# breakout-r2.net
KiCad netlist of a schematic drawn in EAGLE
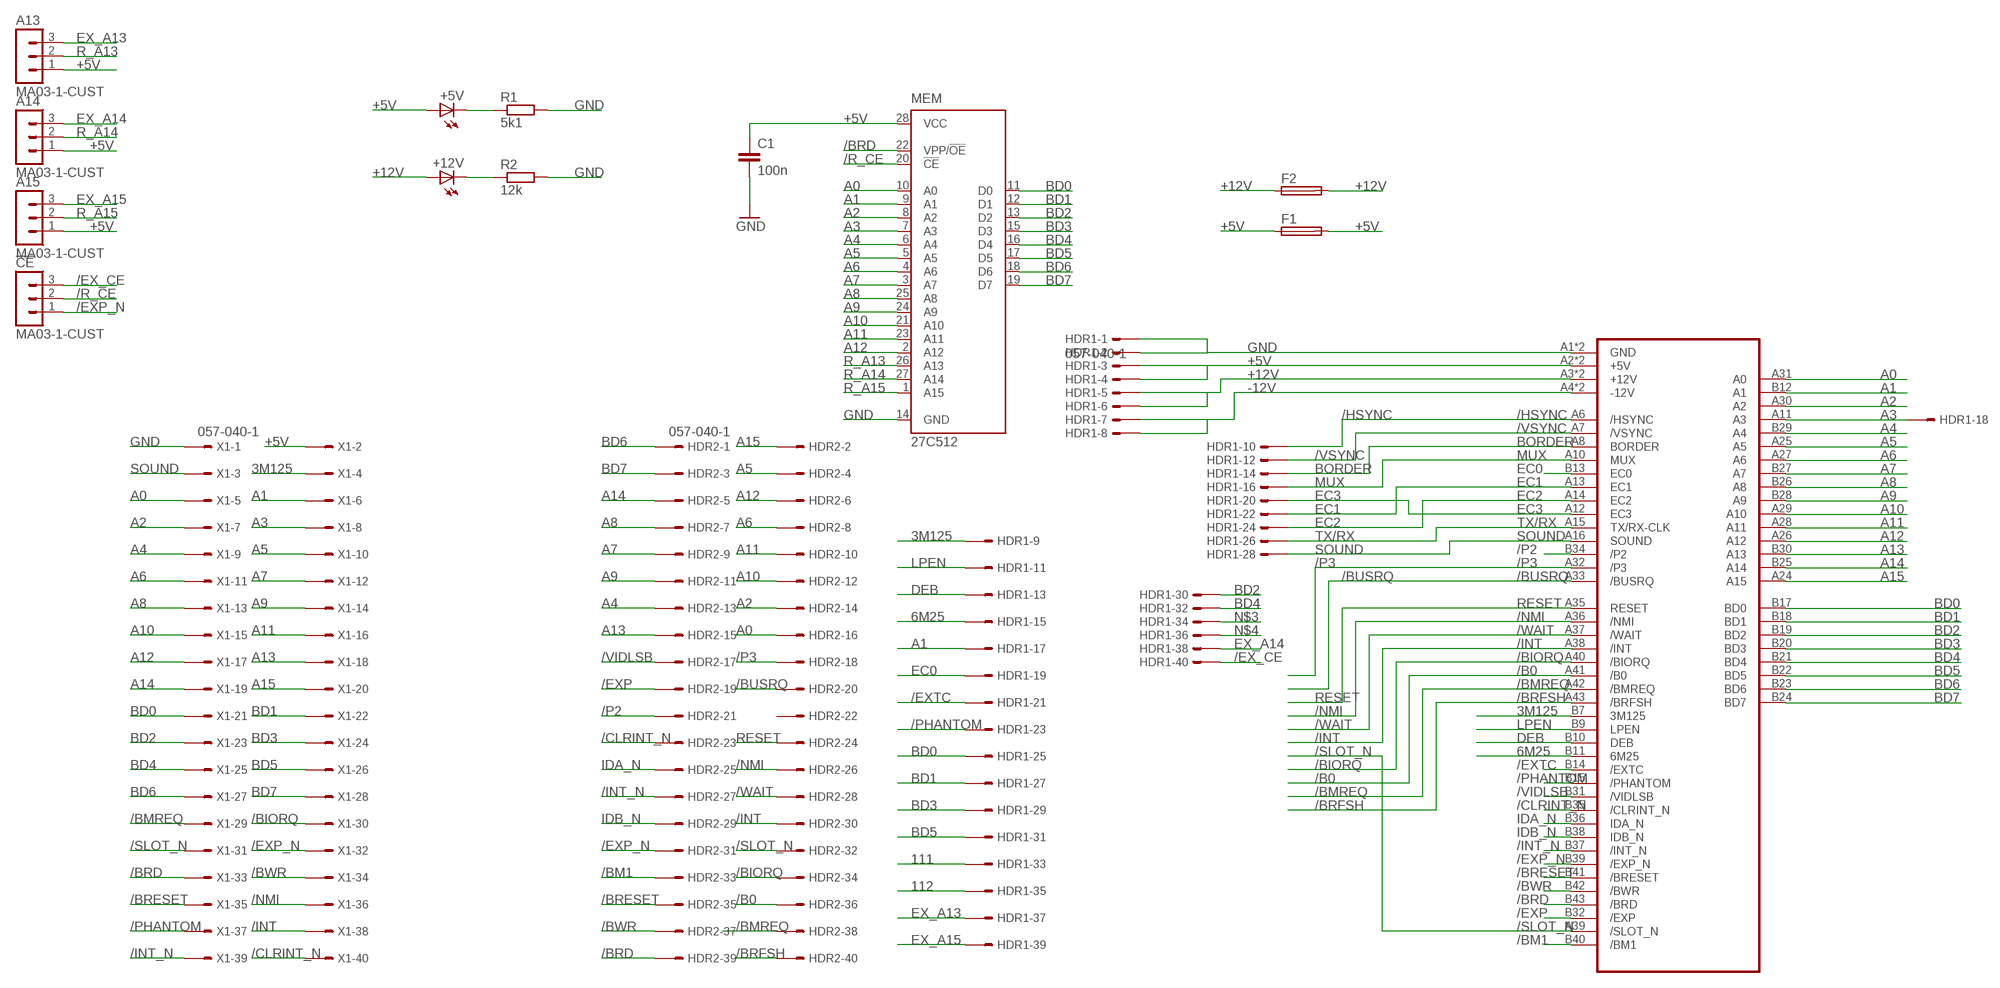
[diagram p0: schematic, sheet 1]

(export (version "E")
  (design (tool "Eeschema 10.0.6"))
  (components
    (comp (ref "!CE")
      (value "MA03-1-CUST")
      (footprint "eagle-import:MA03-1")
      (libsource (lib "eagle-import") (part "MA03-1-CUST"))
    )
    (comp (ref "+5V")
      (value "LED3MM")
      (footprint "eagle-import:LED3MM")
      (libsource (lib "eagle-import") (part "LED3MM"))
    )
    (comp (ref "+12V")
      (value "LED3MM")
      (footprint "eagle-import:LED3MM")
      (libsource (lib "eagle-import") (part "LED3MM"))
    )
    (comp (ref "A13")
      (value "MA03-1-CUST")
      (footprint "eagle-import:MA03-1")
      (libsource (lib "eagle-import") (part "MA03-1-CUST"))
    )
    (comp (ref "A14")
      (value "MA03-1-CUST")
      (footprint "eagle-import:MA03-1")
      (libsource (lib "eagle-import") (part "MA03-1-CUST"))
    )
    (comp (ref "A15")
      (value "MA03-1-CUST")
      (footprint "eagle-import:MA03-1")
      (libsource (lib "eagle-import") (part "MA03-1-CUST"))
    )
    (comp (ref "C1")
      (value "100n")
      (footprint "eagle-import:C025-025X050")
      (libsource (lib "eagle-import") (part "C-EU025-025X050"))
    )
    (comp (ref "F1")
      (value "TE5")
      (footprint "eagle-import:TE5")
      (libsource (lib "eagle-import") (part "TE5"))
    )
    (comp (ref "F2")
      (value "TE5")
      (footprint "eagle-import:TE5")
      (libsource (lib "eagle-import") (part "TE5"))
    )
    (comp (ref "HDR1")
      (value "057-040-1")
      (footprint "eagle-import:057-040-1")
      (libsource (lib "eagle-import") (part "057-040-1"))
    )
    (comp (ref "HDR2")
      (value "057-040-1")
      (footprint "eagle-import:057-040-1")
      (libsource (lib "eagle-import") (part "057-040-1"))
    )
    (comp (ref "MEM")
      (value "27C512")
      (footprint "eagle-import:DIL28-6")
      (libsource (lib "eagle-import") (part "W27C512"))
    )
    (comp (ref "R1")
      (value "5k1")
      (footprint "eagle-import:0204_7")
      (libsource (lib "eagle-import") (part "R-EU_0204/7"))
    )
    (comp (ref "R2")
      (value "12k")
      (footprint "eagle-import:0204_7")
      (libsource (lib "eagle-import") (part "R-EU_0204/7"))
    )
    (comp (ref "U$1")
      (value "TVC-EXP-HBA-COMMON")
      (footprint "eagle-import:TVC-EXP-EDGE")
      (libsource (lib "eagle-import") (part "TVC-EXP-HBA-COMMON"))
    )
    (comp (ref "X1")
      (value "057-040-1")
      (footprint "eagle-import:057-040-1")
      (libsource (lib "eagle-import") (part "057-040-1"))
    )
  )
  (nets
    (net (code "1") (name "/+5V") (class "Default")
      (node (ref "+5V") (pin "A") (pinfunction "A_A") (pintype "passive"))
      (node (ref "A13") (pin "1") (pinfunction "1_1") (pintype "passive"))
      (node (ref "A14") (pin "1") (pinfunction "1_1") (pintype "passive"))
      (node (ref "A15") (pin "1") (pinfunction "1_1") (pintype "passive"))
      (node (ref "C1") (pin "1") (pinfunction "1_1") (pintype "passive"))
      (node (ref "F1") (pin "1") (pinfunction "1_1") (pintype "passive"))
      (node (ref "F1") (pin "2") (pinfunction "2_2") (pintype "passive"))
      (node (ref "HDR1") (pin "3") (pinfunction "S_3") (pintype "passive"))
      (node (ref "HDR1") (pin "4") (pinfunction "S_4") (pintype "passive"))
      (node (ref "MEM") (pin "28") (pinfunction "VCC_28") (pintype "power_in"))
      (node (ref "U$1") (pin "A2") (pinfunction "+5V_A2") (pintype "power_in"))
      (node (ref "U$1") (pin "B2") (pinfunction "+5V_B2") (pintype "power_in"))
      (node (ref "X1") (pin "2") (pinfunction "S_2") (pintype "passive"))
    )
    (net (code "2") (name "/+12V") (class "Default")
      (node (ref "+12V") (pin "A") (pinfunction "A_A") (pintype "passive"))
      (node (ref "F2") (pin "1") (pinfunction "1_1") (pintype "passive"))
      (node (ref "F2") (pin "2") (pinfunction "2_2") (pintype "passive"))
      (node (ref "HDR1") (pin "5") (pinfunction "S_5") (pintype "passive"))
      (node (ref "HDR1") (pin "6") (pinfunction "S_6") (pintype "passive"))
      (node (ref "U$1") (pin "A3") (pinfunction "+12V_A3") (pintype "power_in"))
      (node (ref "U$1") (pin "B3") (pinfunction "+12V_B3") (pintype "power_in"))
    )
    (net (code "3") (name "/-12V") (class "Default")
      (node (ref "HDR1") (pin "7") (pinfunction "S_7") (pintype "passive"))
      (node (ref "HDR1") (pin "8") (pinfunction "S_8") (pintype "passive"))
      (node (ref "U$1") (pin "A4") (pinfunction "-12V_A4") (pintype "power_in"))
      (node (ref "U$1") (pin "B4") (pinfunction "-12V_B4") (pintype "power_in"))
    )
    (net (code "4") (name "/3M125") (class "Default")
      (node (ref "HDR1") (pin "9") (pinfunction "S_9") (pintype "passive"))
      (node (ref "U$1") (pin "B7") (pinfunction "3M125_B7") (pintype "bidirectional"))
      (node (ref "X1") (pin "4") (pinfunction "S_4") (pintype "passive"))
    )
    (net (code "5") (name "/6M25") (class "Default")
      (node (ref "HDR1") (pin "15") (pinfunction "S_15") (pintype "passive"))
      (node (ref "U$1") (pin "B11") (pinfunction "6M25_B11") (pintype "bidirectional"))
    )
    (net (code "6") (name "/111") (class "Default")
      (node (ref "HDR1") (pin "33") (pinfunction "S_33") (pintype "passive"))
    )
    (net (code "7") (name "/112") (class "Default")
      (node (ref "HDR1") (pin "35") (pinfunction "S_35") (pintype "passive"))
    )
    (net (code "8") (name "/A0") (class "Default")
      (node (ref "HDR2") (pin "16") (pinfunction "S_16") (pintype "passive"))
      (node (ref "MEM") (pin "10") (pinfunction "A0_10") (pintype "input"))
      (node (ref "U$1") (pin "A31") (pinfunction "A0_A31") (pintype "bidirectional"))
      (node (ref "X1") (pin "5") (pinfunction "S_5") (pintype "passive"))
    )
    (net (code "9") (name "/A1") (class "Default")
      (node (ref "HDR1") (pin "17") (pinfunction "S_17") (pintype "passive"))
      (node (ref "MEM") (pin "9") (pinfunction "A1_9") (pintype "input"))
      (node (ref "U$1") (pin "B12") (pinfunction "A1_B12") (pintype "bidirectional"))
      (node (ref "X1") (pin "6") (pinfunction "S_6") (pintype "passive"))
    )
    (net (code "10") (name "/A2") (class "Default")
      (node (ref "HDR2") (pin "14") (pinfunction "S_14") (pintype "passive"))
      (node (ref "MEM") (pin "8") (pinfunction "A2_8") (pintype "input"))
      (node (ref "U$1") (pin "A30") (pinfunction "A2_A30") (pintype "bidirectional"))
      (node (ref "X1") (pin "7") (pinfunction "S_7") (pintype "passive"))
    )
    (net (code "11") (name "/A3") (class "Default")
      (node (ref "HDR1") (pin "18") (pinfunction "S_18") (pintype "passive"))
      (node (ref "MEM") (pin "7") (pinfunction "A3_7") (pintype "input"))
      (node (ref "U$1") (pin "A11") (pinfunction "A3_A11") (pintype "bidirectional"))
      (node (ref "X1") (pin "8") (pinfunction "S_8") (pintype "passive"))
    )
    (net (code "12") (name "/A4") (class "Default")
      (node (ref "HDR2") (pin "13") (pinfunction "S_13") (pintype "passive"))
      (node (ref "MEM") (pin "6") (pinfunction "A4_6") (pintype "input"))
      (node (ref "U$1") (pin "B29") (pinfunction "A4_B29") (pintype "bidirectional"))
      (node (ref "X1") (pin "9") (pinfunction "S_9") (pintype "passive"))
    )
    (net (code "13") (name "/A5") (class "Default")
      (node (ref "HDR2") (pin "4") (pinfunction "S_4") (pintype "passive"))
      (node (ref "MEM") (pin "5") (pinfunction "A5_5") (pintype "input"))
      (node (ref "U$1") (pin "A25") (pinfunction "A5_A25") (pintype "bidirectional"))
      (node (ref "X1") (pin "10") (pinfunction "S_10") (pintype "passive"))
    )
    (net (code "14") (name "/A6") (class "Default")
      (node (ref "HDR2") (pin "8") (pinfunction "S_8") (pintype "passive"))
      (node (ref "MEM") (pin "4") (pinfunction "A6_4") (pintype "input"))
      (node (ref "U$1") (pin "A27") (pinfunction "A6_A27") (pintype "bidirectional"))
      (node (ref "X1") (pin "11") (pinfunction "S_11") (pintype "passive"))
    )
    (net (code "15") (name "/A7") (class "Default")
      (node (ref "HDR2") (pin "9") (pinfunction "S_9") (pintype "passive"))
      (node (ref "MEM") (pin "3") (pinfunction "A7_3") (pintype "input"))
      (node (ref "U$1") (pin "B27") (pinfunction "A7_B27") (pintype "bidirectional"))
      (node (ref "X1") (pin "12") (pinfunction "S_12") (pintype "passive"))
    )
    (net (code "16") (name "/A8") (class "Default")
      (node (ref "HDR2") (pin "7") (pinfunction "S_7") (pintype "passive"))
      (node (ref "MEM") (pin "25") (pinfunction "A8_25") (pintype "input"))
      (node (ref "U$1") (pin "B26") (pinfunction "A8_B26") (pintype "bidirectional"))
      (node (ref "X1") (pin "13") (pinfunction "S_13") (pintype "passive"))
    )
    (net (code "17") (name "/A9") (class "Default")
      (node (ref "HDR2") (pin "11") (pinfunction "S_11") (pintype "passive"))
      (node (ref "MEM") (pin "24") (pinfunction "A9_24") (pintype "input"))
      (node (ref "U$1") (pin "B28") (pinfunction "A9_B28") (pintype "bidirectional"))
      (node (ref "X1") (pin "14") (pinfunction "S_14") (pintype "passive"))
    )
    (net (code "18") (name "/A10") (class "Default")
      (node (ref "HDR2") (pin "12") (pinfunction "S_12") (pintype "passive"))
      (node (ref "MEM") (pin "21") (pinfunction "A10_21") (pintype "input"))
      (node (ref "U$1") (pin "A29") (pinfunction "A10_A29") (pintype "bidirectional"))
      (node (ref "X1") (pin "15") (pinfunction "S_15") (pintype "passive"))
    )
    (net (code "19") (name "/A11") (class "Default")
      (node (ref "HDR2") (pin "10") (pinfunction "S_10") (pintype "passive"))
      (node (ref "MEM") (pin "23") (pinfunction "A11_23") (pintype "input"))
      (node (ref "U$1") (pin "A28") (pinfunction "A11_A28") (pintype "bidirectional"))
      (node (ref "X1") (pin "16") (pinfunction "S_16") (pintype "passive"))
    )
    (net (code "20") (name "/A12") (class "Default")
      (node (ref "HDR2") (pin "6") (pinfunction "S_6") (pintype "passive"))
      (node (ref "MEM") (pin "2") (pinfunction "A12_2") (pintype "input"))
      (node (ref "U$1") (pin "A26") (pinfunction "A12_A26") (pintype "bidirectional"))
      (node (ref "X1") (pin "17") (pinfunction "S_17") (pintype "passive"))
    )
    (net (code "21") (name "/A13") (class "Default")
      (node (ref "HDR2") (pin "15") (pinfunction "S_15") (pintype "passive"))
      (node (ref "U$1") (pin "B30") (pinfunction "A13_B30") (pintype "bidirectional"))
      (node (ref "X1") (pin "18") (pinfunction "S_18") (pintype "passive"))
    )
    (net (code "22") (name "/A14") (class "Default")
      (node (ref "HDR2") (pin "5") (pinfunction "S_5") (pintype "passive"))
      (node (ref "U$1") (pin "B25") (pinfunction "A14_B25") (pintype "bidirectional"))
      (node (ref "X1") (pin "19") (pinfunction "S_19") (pintype "passive"))
    )
    (net (code "23") (name "/A15") (class "Default")
      (node (ref "HDR2") (pin "2") (pinfunction "S_2") (pintype "passive"))
      (node (ref "U$1") (pin "A24") (pinfunction "A15_A24") (pintype "bidirectional"))
      (node (ref "X1") (pin "20") (pinfunction "S_20") (pintype "passive"))
    )
    (net (code "24") (name "/BD0") (class "Default")
      (node (ref "HDR1") (pin "25") (pinfunction "S_25") (pintype "passive"))
      (node (ref "MEM") (pin "11") (pinfunction "D0_11") (pintype "tri_state"))
      (node (ref "U$1") (pin "B17") (pinfunction "BD0_B17") (pintype "bidirectional"))
      (node (ref "X1") (pin "21") (pinfunction "S_21") (pintype "passive"))
    )
    (net (code "25") (name "/BD1") (class "Default")
      (node (ref "HDR1") (pin "27") (pinfunction "S_27") (pintype "passive"))
      (node (ref "MEM") (pin "12") (pinfunction "D1_12") (pintype "tri_state"))
      (node (ref "U$1") (pin "B18") (pinfunction "BD1_B18") (pintype "bidirectional"))
      (node (ref "X1") (pin "22") (pinfunction "S_22") (pintype "passive"))
    )
    (net (code "26") (name "/BD2") (class "Default")
      (node (ref "HDR1") (pin "30") (pinfunction "S_30") (pintype "passive"))
      (node (ref "MEM") (pin "13") (pinfunction "D2_13") (pintype "tri_state"))
      (node (ref "U$1") (pin "B19") (pinfunction "BD2_B19") (pintype "bidirectional"))
      (node (ref "X1") (pin "23") (pinfunction "S_23") (pintype "passive"))
    )
    (net (code "27") (name "/BD3") (class "Default")
      (node (ref "HDR1") (pin "29") (pinfunction "S_29") (pintype "passive"))
      (node (ref "MEM") (pin "15") (pinfunction "D3_15") (pintype "tri_state"))
      (node (ref "U$1") (pin "B20") (pinfunction "BD3_B20") (pintype "bidirectional"))
      (node (ref "X1") (pin "24") (pinfunction "S_24") (pintype "passive"))
    )
    (net (code "28") (name "/BD4") (class "Default")
      (node (ref "HDR1") (pin "32") (pinfunction "S_32") (pintype "passive"))
      (node (ref "MEM") (pin "16") (pinfunction "D4_16") (pintype "tri_state"))
      (node (ref "U$1") (pin "B21") (pinfunction "BD4_B21") (pintype "bidirectional"))
      (node (ref "X1") (pin "25") (pinfunction "S_25") (pintype "passive"))
    )
    (net (code "29") (name "/BD5") (class "Default")
      (node (ref "HDR1") (pin "31") (pinfunction "S_31") (pintype "passive"))
      (node (ref "MEM") (pin "17") (pinfunction "D5_17") (pintype "tri_state"))
      (node (ref "U$1") (pin "B22") (pinfunction "BD5_B22") (pintype "bidirectional"))
      (node (ref "X1") (pin "26") (pinfunction "S_26") (pintype "passive"))
    )
    (net (code "30") (name "/BD6") (class "Default")
      (node (ref "HDR2") (pin "1") (pinfunction "S_1") (pintype "passive"))
      (node (ref "MEM") (pin "18") (pinfunction "D6_18") (pintype "tri_state"))
      (node (ref "U$1") (pin "B23") (pinfunction "BD6_B23") (pintype "bidirectional"))
      (node (ref "X1") (pin "27") (pinfunction "S_27") (pintype "passive"))
    )
    (net (code "31") (name "/BD7") (class "Default")
      (node (ref "HDR2") (pin "3") (pinfunction "S_3") (pintype "passive"))
      (node (ref "MEM") (pin "19") (pinfunction "D7_19") (pintype "tri_state"))
      (node (ref "U$1") (pin "B24") (pinfunction "BD7_B24") (pintype "bidirectional"))
      (node (ref "X1") (pin "28") (pinfunction "S_28") (pintype "passive"))
    )
    (net (code "32") (name "/BORDER") (class "Default")
      (node (ref "HDR1") (pin "14") (pinfunction "S_14") (pintype "passive"))
      (node (ref "U$1") (pin "A8") (pinfunction "BORDER_A8") (pintype "bidirectional"))
    )
    (net (code "33") (name "/DEB") (class "Default")
      (node (ref "HDR1") (pin "13") (pinfunction "S_13") (pintype "passive"))
      (node (ref "U$1") (pin "B10") (pinfunction "DEB_B10") (pintype "bidirectional"))
    )
    (net (code "34") (name "/EC0") (class "Default")
      (node (ref "HDR1") (pin "19") (pinfunction "S_19") (pintype "passive"))
      (node (ref "U$1") (pin "B13") (pinfunction "EC0_B13") (pintype "bidirectional"))
    )
    (net (code "35") (name "/EC1") (class "Default")
      (node (ref "HDR1") (pin "22") (pinfunction "S_22") (pintype "passive"))
      (node (ref "U$1") (pin "A13") (pinfunction "EC1_A13") (pintype "bidirectional"))
    )
    (net (code "36") (name "/EC2") (class "Default")
      (node (ref "HDR1") (pin "24") (pinfunction "S_24") (pintype "passive"))
      (node (ref "U$1") (pin "A14") (pinfunction "EC2_A14") (pintype "bidirectional"))
    )
    (net (code "37") (name "/EC3") (class "Default")
      (node (ref "HDR1") (pin "20") (pinfunction "S_20") (pintype "passive"))
      (node (ref "U$1") (pin "A12") (pinfunction "EC3_A12") (pintype "bidirectional"))
    )
    (net (code "38") (name "/EX_A13") (class "Default")
      (node (ref "A13") (pin "3") (pinfunction "3_3") (pintype "passive"))
      (node (ref "HDR1") (pin "37") (pinfunction "S_37") (pintype "passive"))
    )
    (net (code "39") (name "/EX_A14") (class "Default")
      (node (ref "A14") (pin "3") (pinfunction "3_3") (pintype "passive"))
      (node (ref "HDR1") (pin "38") (pinfunction "S_38") (pintype "passive"))
    )
    (net (code "40") (name "/EX_A15") (class "Default")
      (node (ref "A15") (pin "3") (pinfunction "3_3") (pintype "passive"))
      (node (ref "HDR1") (pin "39") (pinfunction "S_39") (pintype "passive"))
    )
    (net (code "41") (name "/IDA_N") (class "Default")
      (node (ref "HDR2") (pin "25") (pinfunction "S_25") (pintype "passive"))
      (node (ref "U$1") (pin "B36") (pinfunction "IDA_N_B36") (pintype "bidirectional"))
    )
    (net (code "42") (name "/IDB_N") (class "Default")
      (node (ref "HDR2") (pin "29") (pinfunction "S_29") (pintype "passive"))
      (node (ref "U$1") (pin "B38") (pinfunction "IDB_N_B38") (pintype "bidirectional"))
    )
    (net (code "43") (name "/LPEN") (class "Default")
      (node (ref "HDR1") (pin "11") (pinfunction "S_11") (pintype "passive"))
      (node (ref "U$1") (pin "B9") (pinfunction "LPEN_B9") (pintype "bidirectional"))
    )
    (net (code "44") (name "/MUX") (class "Default")
      (node (ref "HDR1") (pin "16") (pinfunction "S_16") (pintype "passive"))
      (node (ref "U$1") (pin "A10") (pinfunction "MUX_A10") (pintype "bidirectional"))
    )
    (net (code "45") (name "/N$3") (class "Default")
      (node (ref "HDR1") (pin "34") (pinfunction "S_34") (pintype "passive"))
    )
    (net (code "46") (name "/N$4") (class "Default")
      (node (ref "HDR1") (pin "36") (pinfunction "S_36") (pintype "passive"))
    )
    (net (code "47") (name "/RESET") (class "Default")
      (node (ref "HDR2") (pin "24") (pinfunction "S_24") (pintype "passive"))
      (node (ref "U$1") (pin "A35") (pinfunction "RESET_A35") (pintype "bidirectional"))
    )
    (net (code "48") (name "/R_A13") (class "Default")
      (node (ref "A13") (pin "2") (pinfunction "2_2") (pintype "passive"))
      (node (ref "MEM") (pin "26") (pinfunction "A13_26") (pintype "input"))
    )
    (net (code "49") (name "/R_A14") (class "Default")
      (node (ref "A14") (pin "2") (pinfunction "2_2") (pintype "passive"))
      (node (ref "MEM") (pin "27") (pinfunction "A14_27") (pintype "input"))
    )
    (net (code "50") (name "/R_A15") (class "Default")
      (node (ref "A15") (pin "2") (pinfunction "2_2") (pintype "passive"))
      (node (ref "MEM") (pin "1") (pinfunction "A15_1") (pintype "input"))
    )
    (net (code "51") (name "/SOUND") (class "Default")
      (node (ref "HDR1") (pin "28") (pinfunction "S_28") (pintype "passive"))
      (node (ref "U$1") (pin "A16") (pinfunction "SOUND_A16") (pintype "bidirectional"))
      (node (ref "X1") (pin "3") (pinfunction "S_3") (pintype "passive"))
    )
    (net (code "52") (name "/TX{slash}RX") (class "Default")
      (node (ref "HDR1") (pin "26") (pinfunction "S_26") (pintype "passive"))
      (node (ref "U$1") (pin "A15") (pinfunction "TX/RX-CLK_A15") (pintype "bidirectional"))
    )
    (net (code "53") (name "/{slash}B0") (class "Default")
      (node (ref "HDR2") (pin "36") (pinfunction "S_36") (pintype "passive"))
      (node (ref "U$1") (pin "A41") (pinfunction "/B0_A41") (pintype "bidirectional"))
    )
    (net (code "54") (name "/{slash}BIORQ") (class "Default")
      (node (ref "HDR2") (pin "34") (pinfunction "S_34") (pintype "passive"))
      (node (ref "U$1") (pin "A40") (pinfunction "/BIORQ_A40") (pintype "output"))
      (node (ref "X1") (pin "30") (pinfunction "S_30") (pintype "passive"))
    )
    (net (code "55") (name "/{slash}BM1") (class "Default")
      (node (ref "HDR2") (pin "33") (pinfunction "S_33") (pintype "passive"))
      (node (ref "U$1") (pin "B40") (pinfunction "/BM1_B40") (pintype "bidirectional"))
    )
    (net (code "56") (name "/{slash}BMREQ") (class "Default")
      (node (ref "HDR2") (pin "38") (pinfunction "S_38") (pintype "passive"))
      (node (ref "U$1") (pin "A42") (pinfunction "/BMREQ_A42") (pintype "output"))
      (node (ref "X1") (pin "29") (pinfunction "S_29") (pintype "passive"))
    )
    (net (code "57") (name "/{slash}BRD") (class "Default")
      (node (ref "HDR2") (pin "39") (pinfunction "S_39") (pintype "passive"))
      (node (ref "MEM") (pin "22") (pinfunction "VPP/~{OE}_22") (pintype "input"))
      (node (ref "U$1") (pin "B43") (pinfunction "/BRD_B43") (pintype "output"))
      (node (ref "X1") (pin "33") (pinfunction "S_33") (pintype "passive"))
    )
    (net (code "58") (name "/{slash}BRESET") (class "Default")
      (node (ref "HDR2") (pin "35") (pinfunction "S_35") (pintype "passive"))
      (node (ref "U$1") (pin "B41") (pinfunction "/BRESET_B41") (pintype "bidirectional"))
      (node (ref "X1") (pin "35") (pinfunction "S_35") (pintype "passive"))
    )
    (net (code "59") (name "/{slash}BRFSH") (class "Default")
      (node (ref "HDR2") (pin "40") (pinfunction "S_40") (pintype "passive"))
      (node (ref "U$1") (pin "A43") (pinfunction "/BRFSH_A43") (pintype "bidirectional"))
    )
    (net (code "60") (name "/{slash}BUSRQ") (class "Default")
      (node (ref "HDR2") (pin "20") (pinfunction "S_20") (pintype "passive"))
      (node (ref "U$1") (pin "A33") (pinfunction "/BUSRQ_A33") (pintype "bidirectional"))
    )
    (net (code "61") (name "/{slash}BWR") (class "Default")
      (node (ref "HDR2") (pin "37") (pinfunction "S_37") (pintype "passive"))
      (node (ref "U$1") (pin "B42") (pinfunction "/BWR_B42") (pintype "output"))
      (node (ref "X1") (pin "34") (pinfunction "S_34") (pintype "passive"))
    )
    (net (code "62") (name "/{slash}CLRINT_N") (class "Default")
      (node (ref "HDR2") (pin "23") (pinfunction "S_23") (pintype "passive"))
      (node (ref "U$1") (pin "B35") (pinfunction "/CLRINT_N_B35") (pintype "bidirectional"))
      (node (ref "X1") (pin "40") (pinfunction "S_40") (pintype "passive"))
    )
    (net (code "63") (name "/{slash}EXP") (class "Default")
      (node (ref "HDR2") (pin "19") (pinfunction "S_19") (pintype "passive"))
      (node (ref "U$1") (pin "B32") (pinfunction "/EXP_B32") (pintype "bidirectional"))
    )
    (net (code "64") (name "/{slash}EXP_N") (class "Default")
      (node (ref "!CE") (pin "1") (pinfunction "1_1") (pintype "passive"))
      (node (ref "HDR2") (pin "31") (pinfunction "S_31") (pintype "passive"))
      (node (ref "U$1") (pin "B39") (pinfunction "/EXP_N_B39") (pintype "bidirectional"))
      (node (ref "X1") (pin "32") (pinfunction "S_32") (pintype "passive"))
    )
    (net (code "65") (name "/{slash}EXTC") (class "Default")
      (node (ref "HDR1") (pin "21") (pinfunction "S_21") (pintype "passive"))
      (node (ref "U$1") (pin "B14") (pinfunction "/EXTC_B14") (pintype "bidirectional"))
    )
    (net (code "66") (name "/{slash}EX_CE") (class "Default")
      (node (ref "!CE") (pin "3") (pinfunction "3_3") (pintype "passive"))
      (node (ref "HDR1") (pin "40") (pinfunction "S_40") (pintype "passive"))
    )
    (net (code "67") (name "/{slash}HSYNC") (class "Default")
      (node (ref "HDR1") (pin "10") (pinfunction "S_10") (pintype "passive"))
      (node (ref "U$1") (pin "A6") (pinfunction "/HSYNC_A6") (pintype "bidirectional"))
    )
    (net (code "68") (name "/{slash}INT") (class "Default")
      (node (ref "HDR2") (pin "30") (pinfunction "S_30") (pintype "passive"))
      (node (ref "U$1") (pin "A38") (pinfunction "/INT_A38") (pintype "bidirectional"))
      (node (ref "X1") (pin "38") (pinfunction "S_38") (pintype "passive"))
    )
    (net (code "69") (name "/{slash}INT_N") (class "Default")
      (node (ref "HDR2") (pin "27") (pinfunction "S_27") (pintype "passive"))
      (node (ref "U$1") (pin "B37") (pinfunction "/INT_N_B37") (pintype "bidirectional"))
      (node (ref "X1") (pin "39") (pinfunction "S_39") (pintype "passive"))
    )
    (net (code "70") (name "/{slash}NMI") (class "Default")
      (node (ref "HDR2") (pin "26") (pinfunction "S_26") (pintype "passive"))
      (node (ref "U$1") (pin "A36") (pinfunction "/NMI_A36") (pintype "bidirectional"))
      (node (ref "X1") (pin "36") (pinfunction "S_36") (pintype "passive"))
    )
    (net (code "71") (name "/{slash}P2") (class "Default")
      (node (ref "HDR2") (pin "21") (pinfunction "S_21") (pintype "passive"))
      (node (ref "U$1") (pin "B34") (pinfunction "/P2_B34") (pintype "bidirectional"))
    )
    (net (code "72") (name "/{slash}P3") (class "Default")
      (node (ref "HDR2") (pin "18") (pinfunction "S_18") (pintype "passive"))
      (node (ref "U$1") (pin "A32") (pinfunction "/P3_A32") (pintype "bidirectional"))
    )
    (net (code "73") (name "/{slash}PHANTOM") (class "Default")
      (node (ref "HDR1") (pin "23") (pinfunction "S_23") (pintype "passive"))
      (node (ref "U$1") (pin "B15") (pinfunction "/PHANTOM_B15") (pintype "bidirectional"))
      (node (ref "X1") (pin "37") (pinfunction "S_37") (pintype "passive"))
    )
    (net (code "74") (name "/{slash}R_CE") (class "Default")
      (node (ref "!CE") (pin "2") (pinfunction "2_2") (pintype "passive"))
      (node (ref "MEM") (pin "20") (pinfunction "~{CE}_20") (pintype "input"))
    )
    (net (code "75") (name "/{slash}SLOT_N") (class "Default")
      (node (ref "HDR2") (pin "32") (pinfunction "S_32") (pintype "passive"))
      (node (ref "U$1") (pin "A39") (pinfunction "/SLOT_N_A39") (pintype "input"))
      (node (ref "X1") (pin "31") (pinfunction "S_31") (pintype "passive"))
    )
    (net (code "76") (name "/{slash}VIDLSB") (class "Default")
      (node (ref "HDR2") (pin "17") (pinfunction "S_17") (pintype "passive"))
      (node (ref "U$1") (pin "B31") (pinfunction "/VIDLSB_B31") (pintype "bidirectional"))
    )
    (net (code "77") (name "/{slash}VSYNC") (class "Default")
      (node (ref "HDR1") (pin "12") (pinfunction "S_12") (pintype "passive"))
      (node (ref "U$1") (pin "A7") (pinfunction "/VSYNC_A7") (pintype "bidirectional"))
    )
    (net (code "78") (name "/{slash}WAIT") (class "Default")
      (node (ref "HDR2") (pin "28") (pinfunction "S_28") (pintype "passive"))
      (node (ref "U$1") (pin "A37") (pinfunction "/WAIT_A37") (pintype "bidirectional"))
    )
    (net (code "79") (name "GND") (class "Default")
      (node (ref "C1") (pin "2") (pinfunction "2_2") (pintype "passive"))
      (node (ref "HDR1") (pin "1") (pinfunction "S_1") (pintype "passive"))
      (node (ref "HDR1") (pin "2") (pinfunction "S_2") (pintype "passive"))
      (node (ref "MEM") (pin "14") (pinfunction "GND_14") (pintype "power_in"))
      (node (ref "R1") (pin "2") (pinfunction "2_2") (pintype "passive"))
      (node (ref "R2") (pin "2") (pinfunction "2_2") (pintype "passive"))
      (node (ref "U$1") (pin "A1") (pinfunction "GND_A1") (pintype "power_in"))
      (node (ref "U$1") (pin "B1") (pinfunction "GND_B1") (pintype "power_in"))
      (node (ref "X1") (pin "1") (pinfunction "S_1") (pintype "passive"))
    )
    (net (code "80") (name "Net-(+5V-C)") (class "Default")
      (node (ref "+5V") (pin "K") (pinfunction "C_K") (pintype "passive"))
      (node (ref "R1") (pin "1") (pinfunction "1_1") (pintype "passive"))
    )
    (net (code "81") (name "Net-(+12V-C)") (class "Default")
      (node (ref "+12V") (pin "K") (pinfunction "C_K") (pintype "passive"))
      (node (ref "R2") (pin "1") (pinfunction "1_1") (pintype "passive"))
    )
    (net (code "82") (name "unconnected-(HDR2O-S-Pad22)") (class "Default")
      (node (ref "HDR2") (pin "22") (pinfunction "S_22") (pintype "passive"))
    )
  )
)
